# airball_sensor_board_v5.net
KiCad netlist of a schematic drawn in EAGLE
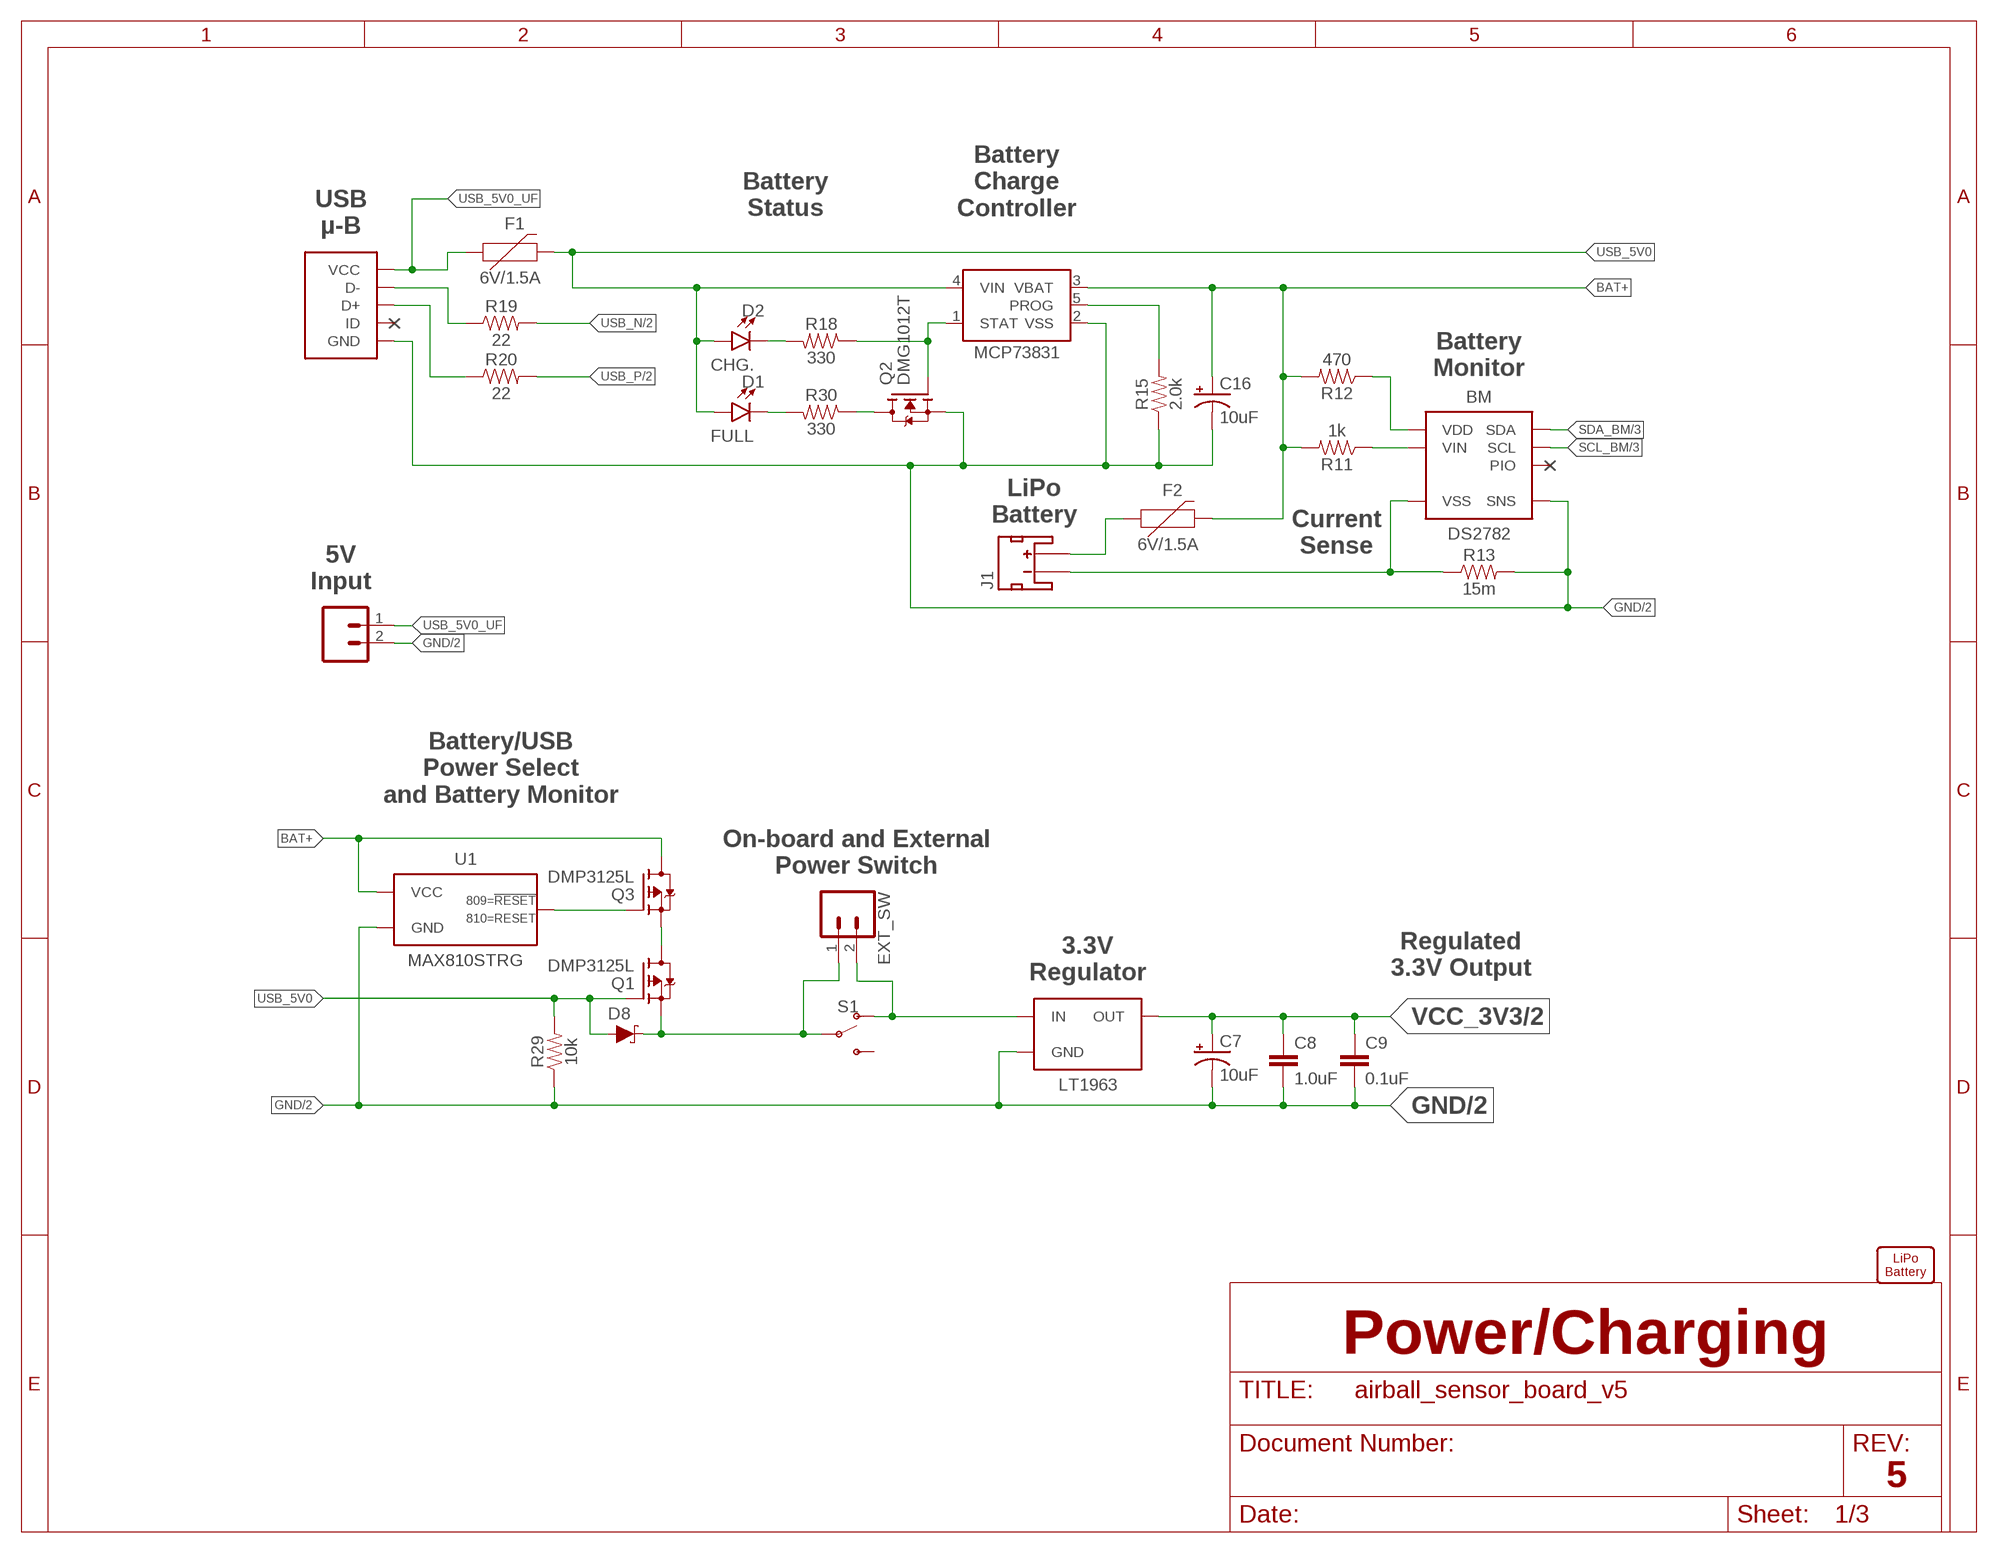
[diagram p0: schematic, sheet 1]
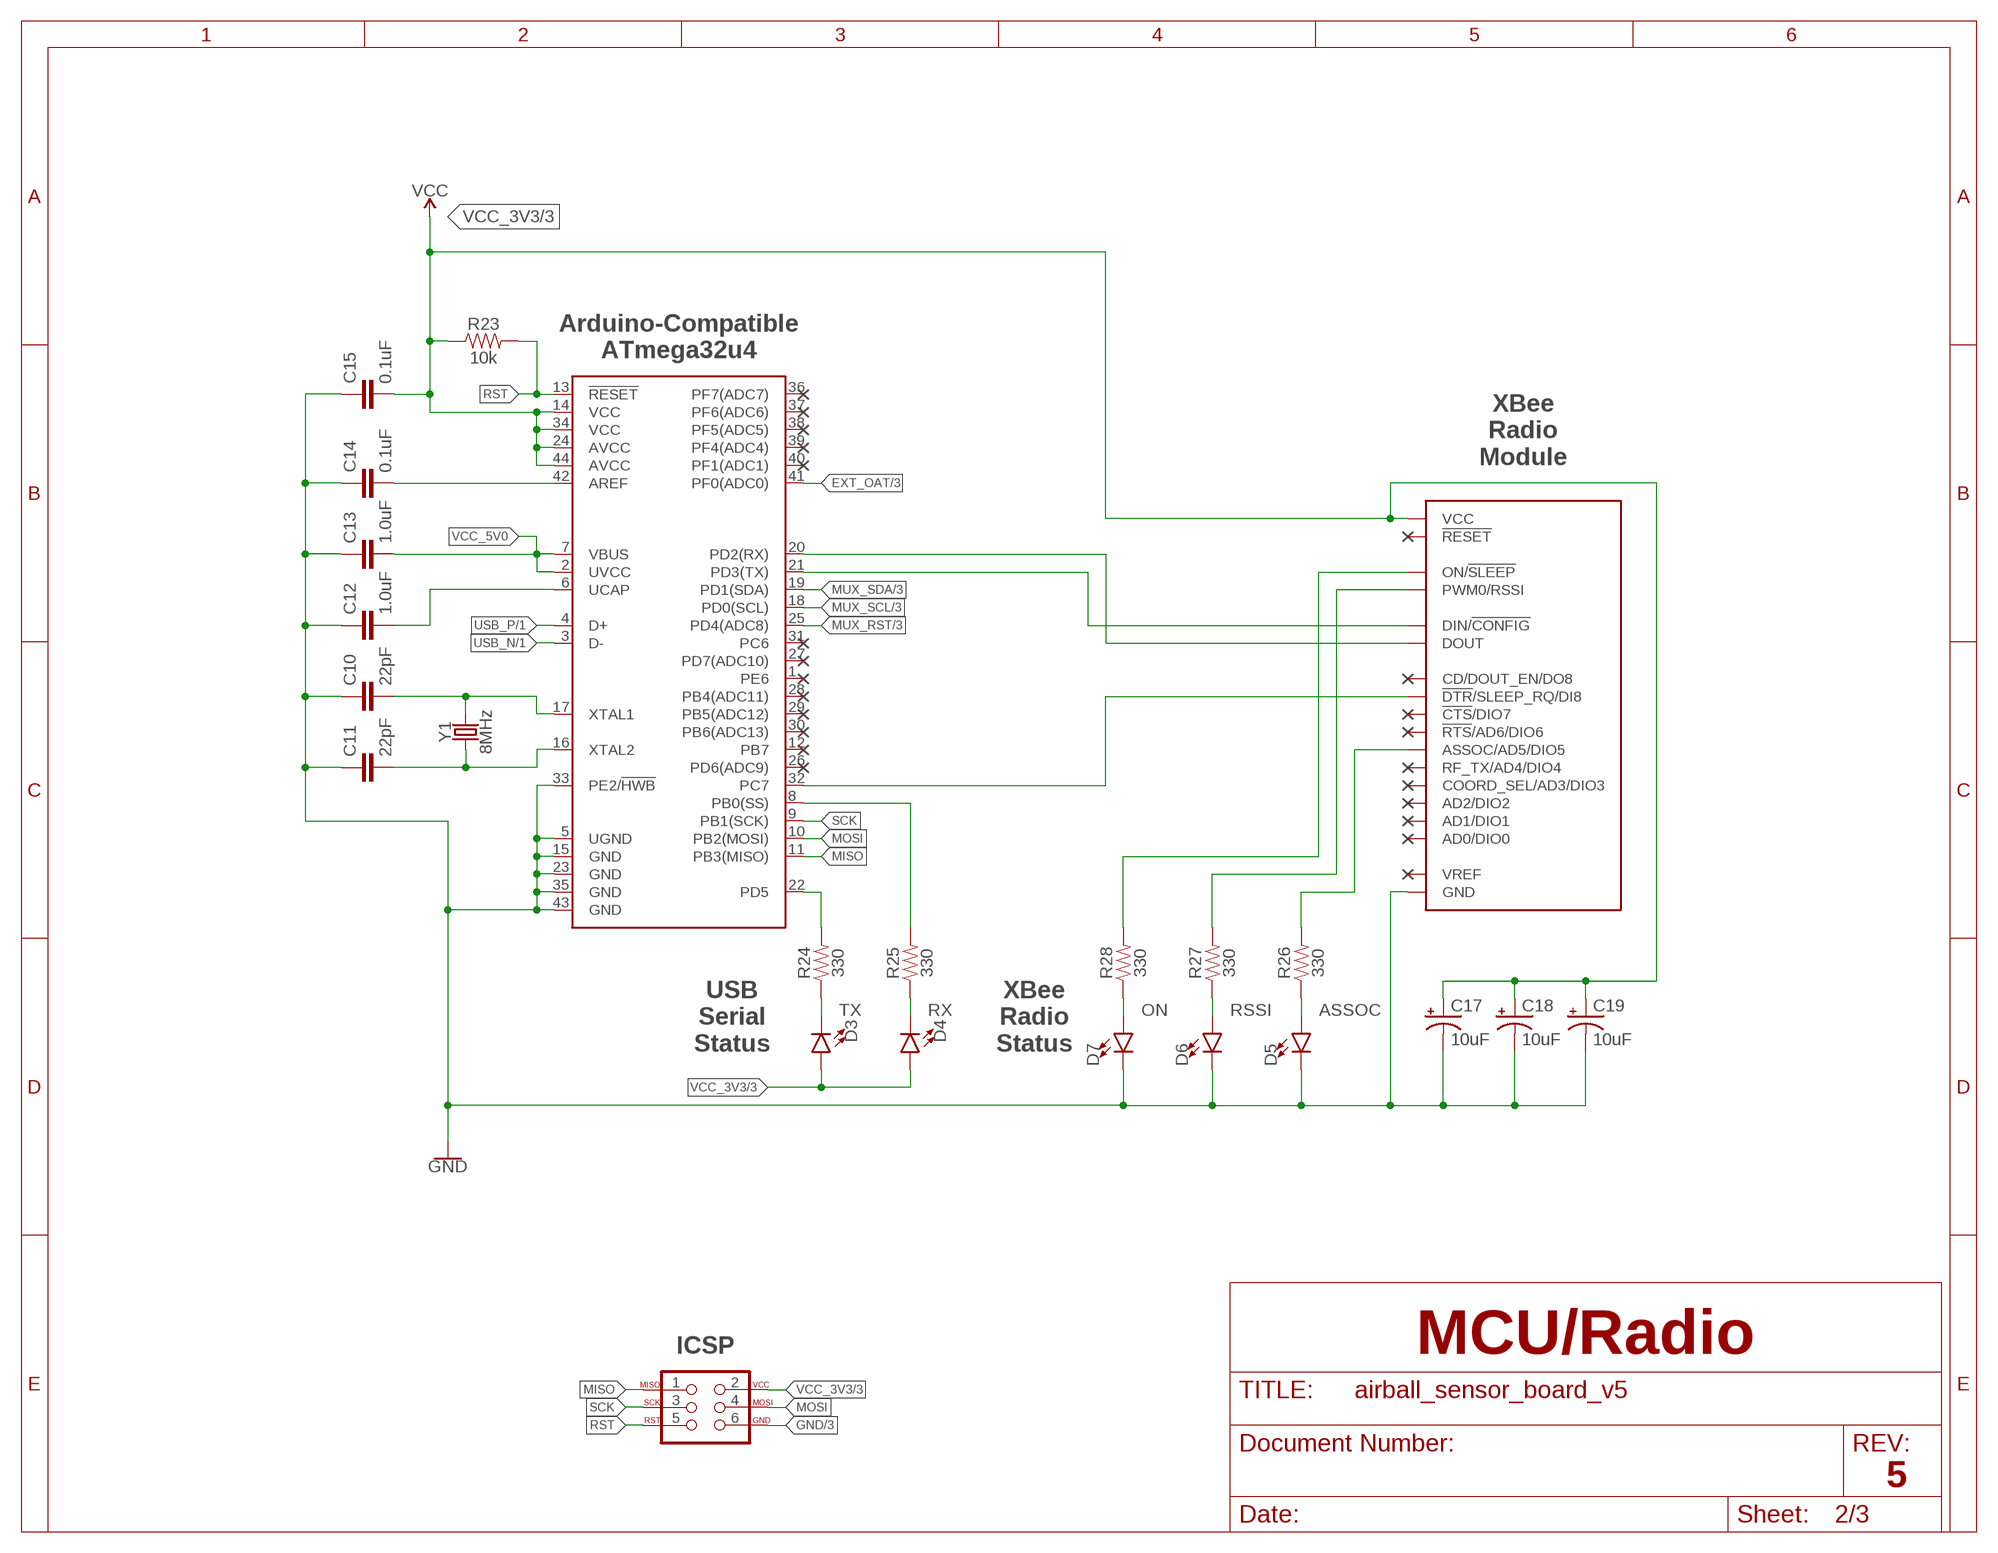
[diagram p1: schematic, sheet 2]
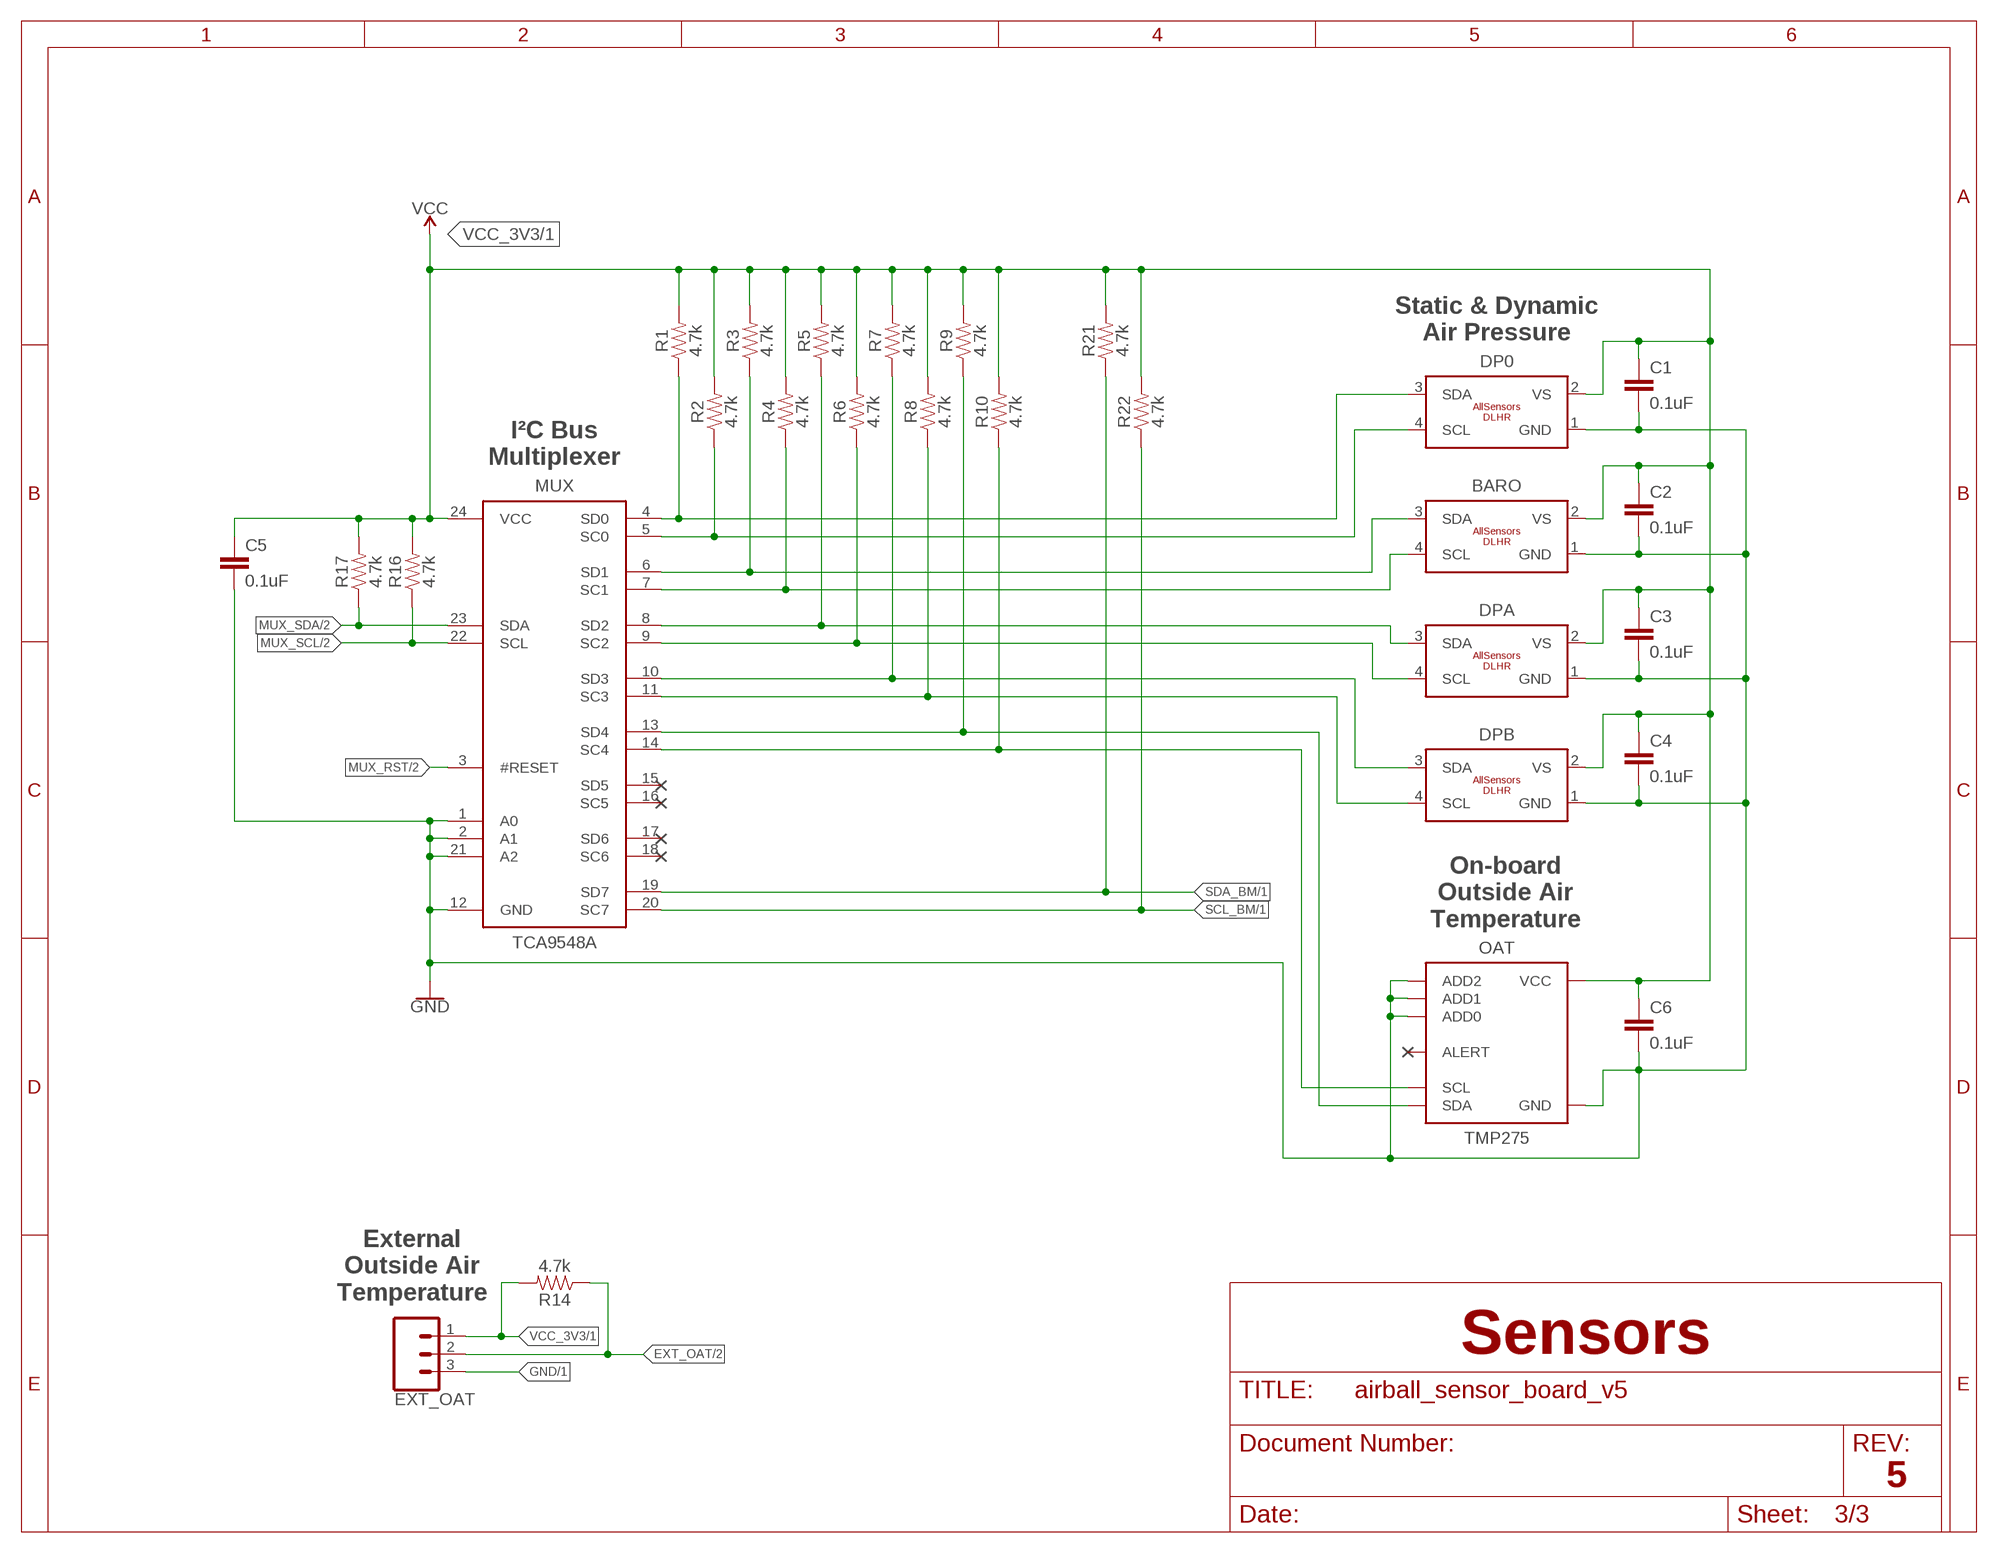
[diagram p2: schematic, sheet 3]

(export (version "E")
  (design (tool "Eeschema 10.0.6"))
  (components
    (comp (ref "BARO")
      (value "ALLSENSORS_DLHR_I2C-E1BD")
      (footprint "eagle-import:ALLSENSORS_E1BD")
      (libsource (lib "eagle-import") (part "ALLSENSORS_DLHR_I2C-E1BD"))
    )
    (comp (ref "C1")
      (value "0.1uF")
      (footprint "eagle-import:0603")
      (libsource (lib "eagle-import") (part "0.1UF-0603-25V-5%"))
    )
    (comp (ref "C2")
      (value "0.1uF")
      (footprint "eagle-import:0603")
      (libsource (lib "eagle-import") (part "0.1UF-0603-25V-5%"))
    )
    (comp (ref "C3")
      (value "0.1uF")
      (footprint "eagle-import:0603")
      (libsource (lib "eagle-import") (part "0.1UF-0603-25V-5%"))
    )
    (comp (ref "C4")
      (value "0.1uF")
      (footprint "eagle-import:0603")
      (libsource (lib "eagle-import") (part "0.1UF-0603-25V-5%"))
    )
    (comp (ref "C5")
      (value "0.1uF")
      (footprint "eagle-import:0603")
      (libsource (lib "eagle-import") (part "0.1UF-0603-25V-5%"))
    )
    (comp (ref "C6")
      (value "0.1uF")
      (footprint "eagle-import:0603")
      (libsource (lib "eagle-import") (part "0.1UF-0603-25V-5%"))
    )
    (comp (ref "DP0")
      (value "ALLSENSORS_DLHR_I2C-E1BD")
      (footprint "eagle-import:ALLSENSORS_E1BD")
      (libsource (lib "eagle-import") (part "ALLSENSORS_DLHR_I2C-E1BD"))
    )
    (comp (ref "DPA")
      (value "ALLSENSORS_DLHR_I2C-E1BD")
      (footprint "eagle-import:ALLSENSORS_E1BD")
      (libsource (lib "eagle-import") (part "ALLSENSORS_DLHR_I2C-E1BD"))
    )
    (comp (ref "DPB")
      (value "ALLSENSORS_DLHR_I2C-E1BD")
      (footprint "eagle-import:ALLSENSORS_E1BD")
      (libsource (lib "eagle-import") (part "ALLSENSORS_DLHR_I2C-E1BD"))
    )
    (comp (ref "EXT_OAT")
      (value "CONN_03")
      (footprint "eagle-import:1X03")
      (libsource (lib "eagle-import") (part "CONN_03"))
    )
    (comp (ref "MUX")
      (value "TCA9548A")
      (footprint "eagle-import:TSSOP24")
      (libsource (lib "eagle-import") (part "TCA9548ATSSOP24"))
    )
    (comp (ref "OAT")
      (value "TMP275")
      (footprint "eagle-import:SOIC8")
      (libsource (lib "eagle-import") (part "LM75-8PIN"))
    )
    (comp (ref "R1")
      (value "4.7k")
      (footprint "eagle-import:0603")
      (libsource (lib "eagle-import") (part "4.7KOHM-0603-1/10W-1%"))
    )
    (comp (ref "R2")
      (value "4.7k")
      (footprint "eagle-import:0603")
      (libsource (lib "eagle-import") (part "4.7KOHM-0603-1/10W-1%"))
    )
    (comp (ref "R3")
      (value "4.7k")
      (footprint "eagle-import:0603")
      (libsource (lib "eagle-import") (part "4.7KOHM-0603-1/10W-1%"))
    )
    (comp (ref "R4")
      (value "4.7k")
      (footprint "eagle-import:0603")
      (libsource (lib "eagle-import") (part "4.7KOHM-0603-1/10W-1%"))
    )
    (comp (ref "R5")
      (value "4.7k")
      (footprint "eagle-import:0603")
      (libsource (lib "eagle-import") (part "4.7KOHM-0603-1/10W-1%"))
    )
    (comp (ref "R6")
      (value "4.7k")
      (footprint "eagle-import:0603")
      (libsource (lib "eagle-import") (part "4.7KOHM-0603-1/10W-1%"))
    )
    (comp (ref "R7")
      (value "4.7k")
      (footprint "eagle-import:0603")
      (libsource (lib "eagle-import") (part "4.7KOHM-0603-1/10W-1%"))
    )
    (comp (ref "R8")
      (value "4.7k")
      (footprint "eagle-import:0603")
      (libsource (lib "eagle-import") (part "4.7KOHM-0603-1/10W-1%"))
    )
    (comp (ref "R9")
      (value "4.7k")
      (footprint "eagle-import:0603")
      (libsource (lib "eagle-import") (part "4.7KOHM-0603-1/10W-1%"))
    )
    (comp (ref "R10")
      (value "4.7k")
      (footprint "eagle-import:0603")
      (libsource (lib "eagle-import") (part "4.7KOHM-0603-1/10W-1%"))
    )
    (comp (ref "R14")
      (value "4.7k")
      (footprint "eagle-import:0603")
      (libsource (lib "eagle-import") (part "4.7KOHM-0603-1/10W-1%"))
    )
    (comp (ref "R16")
      (value "4.7k")
      (footprint "eagle-import:0603")
      (libsource (lib "eagle-import") (part "4.7KOHM-0603-1/10W-1%"))
    )
    (comp (ref "R17")
      (value "4.7k")
      (footprint "eagle-import:0603")
      (libsource (lib "eagle-import") (part "4.7KOHM-0603-1/10W-1%"))
    )
    (comp (ref "R21")
      (value "4.7k")
      (footprint "eagle-import:0603")
      (libsource (lib "eagle-import") (part "4.7KOHM-0603-1/10W-1%"))
    )
    (comp (ref "R22")
      (value "4.7k")
      (footprint "eagle-import:0603")
      (libsource (lib "eagle-import") (part "4.7KOHM-0603-1/10W-1%"))
    )
    (comp (ref "C10")
      (value "22pF")
      (footprint "eagle-import:0603")
      (libsource (lib "eagle-import") (part "22PF-0603-50V-5%"))
    )
    (comp (ref "C11")
      (value "22pF")
      (footprint "eagle-import:0603")
      (libsource (lib "eagle-import") (part "22PF-0603-50V-5%"))
    )
    (comp (ref "C12")
      (value "1.0uF")
      (footprint "eagle-import:0603")
      (libsource (lib "eagle-import") (part "1.0UF-0603-16V-10%"))
    )
    (comp (ref "C13")
      (value "1.0uF")
      (footprint "eagle-import:0603")
      (libsource (lib "eagle-import") (part "1.0UF-0603-16V-10%"))
    )
    (comp (ref "C14")
      (value "0.1uF")
      (footprint "eagle-import:0603")
      (libsource (lib "eagle-import") (part "0.1UF-0603-25V-5%"))
    )
    (comp (ref "C15")
      (value "0.1uF")
      (footprint "eagle-import:0603")
      (libsource (lib "eagle-import") (part "0.1UF-0603-25V-5%"))
    )
    (comp (ref "C17")
      (value "10uF")
      (footprint "eagle-import:EIA3216")
      (libsource (lib "eagle-import") (part "10UF-POLAR-EIA3216-16V-10%(TANT)"))
    )
    (comp (ref "C18")
      (value "10uF")
      (footprint "eagle-import:EIA3216")
      (libsource (lib "eagle-import") (part "10UF-POLAR-EIA3216-16V-10%(TANT)"))
    )
    (comp (ref "C19")
      (value "10uF")
      (footprint "eagle-import:EIA3216")
      (libsource (lib "eagle-import") (part "10UF-POLAR-EIA3216-16V-10%(TANT)"))
    )
    (comp (ref "D3")
      (value "LED0603")
      (footprint "eagle-import:LED-0603")
      (libsource (lib "eagle-import") (part "LED0603"))
    )
    (comp (ref "D4")
      (value "LED0603")
      (footprint "eagle-import:LED-0603")
      (libsource (lib "eagle-import") (part "LED0603"))
    )
    (comp (ref "D5")
      (value "LED0603")
      (footprint "eagle-import:LED-0603")
      (libsource (lib "eagle-import") (part "LED0603"))
    )
    (comp (ref "D6")
      (value "LED0603")
      (footprint "eagle-import:LED-0603")
      (libsource (lib "eagle-import") (part "LED0603"))
    )
    (comp (ref "D7")
      (value "LED0603")
      (footprint "eagle-import:LED-0603")
      (libsource (lib "eagle-import") (part "LED0603"))
    )
    (comp (ref "ICSP")
      (value "AVR_SPI_PROG_3X2PTH")
      (footprint "eagle-import:2X3")
      (libsource (lib "eagle-import") (part "AVR_SPI_PROG_3X2PTH"))
    )
    (comp (ref "MCU")
      (value "32U4")
      (footprint "eagle-import:TQFP44")
      (libsource (lib "eagle-import") (part "ATMEGA32U4TQFP-44"))
    )
    (comp (ref "R23")
      (value "10k")
      (footprint "eagle-import:0603")
      (libsource (lib "eagle-import") (part "10KOHM-0603-1/10W-1%"))
    )
    (comp (ref "R24")
      (value "330")
      (footprint "eagle-import:0603")
      (libsource (lib "eagle-import") (part "330OHM-0603-1/10W-1%"))
    )
    (comp (ref "R25")
      (value "330")
      (footprint "eagle-import:0603")
      (libsource (lib "eagle-import") (part "330OHM-0603-1/10W-1%"))
    )
    (comp (ref "R26")
      (value "330")
      (footprint "eagle-import:0603")
      (libsource (lib "eagle-import") (part "330OHM-0603-1/10W-1%"))
    )
    (comp (ref "R27")
      (value "330")
      (footprint "eagle-import:0603")
      (libsource (lib "eagle-import") (part "330OHM-0603-1/10W-1%"))
    )
    (comp (ref "R28")
      (value "330")
      (footprint "eagle-import:0603")
      (libsource (lib "eagle-import") (part "330OHM-0603-1/10W-1%"))
    )
    (comp (ref "XBEE")
      (value "XBEE-PRO-SMD")
      (footprint "eagle-import:XBEE-PRO-SMD")
      (libsource (lib "eagle-import") (part "XBEE-PRO-SMD"))
    )
    (comp (ref "Y1")
      (value "8MHz")
      (footprint "eagle-import:CRYSTAL-SMD-5X3.2-4PAD")
      (libsource (lib "eagle-import") (part "CRYSTAL-8MHZSMD-5X3.2"))
    )
    (comp (ref "BM")
      (value "DS2782")
      (footprint "eagle-import:TSSOP8")
      (libsource (lib "eagle-import") (part "DS2782"))
    )
    (comp (ref "C7")
      (value "10uF")
      (footprint "eagle-import:EIA3216")
      (libsource (lib "eagle-import") (part "10UF-POLAR-EIA3216-16V-10%(TANT)"))
    )
    (comp (ref "C8")
      (value "1.0uF")
      (footprint "eagle-import:0603")
      (libsource (lib "eagle-import") (part "1.0UF-0603-16V-10%"))
    )
    (comp (ref "C9")
      (value "0.1uF")
      (footprint "eagle-import:0603")
      (libsource (lib "eagle-import") (part "0.1UF-0603-25V-5%"))
    )
    (comp (ref "C16")
      (value "10uF")
      (footprint "eagle-import:EIA3216")
      (libsource (lib "eagle-import") (part "10UF-POLAR-EIA3216-16V-10%(TANT)"))
    )
    (comp (ref "CC")
      (value "MCP73831")
      (footprint "eagle-import:SOT23-5")
      (libsource (lib "eagle-import") (part "MCP73831"))
    )
    (comp (ref "D1")
      (value "LED0603")
      (footprint "eagle-import:LED-0603")
      (libsource (lib "eagle-import") (part "LED0603"))
    )
    (comp (ref "D2")
      (value "LED0603")
      (footprint "eagle-import:LED-0603")
      (libsource (lib "eagle-import") (part "LED0603"))
    )
    (comp (ref "D8")
      (value "DIODE-SCHOTTKY-BAT20J")
      (footprint "eagle-import:SOD-323")
      (libsource (lib "eagle-import") (part "DIODE-SCHOTTKY-BAT20J"))
    )
    (comp (ref "EXT_POWER")
      (value "CONN_02")
      (footprint "eagle-import:1X02")
      (libsource (lib "eagle-import") (part "CONN_02"))
    )
    (comp (ref "EXT_SW")
      (value "CONN_02")
      (footprint "eagle-import:1X02")
      (libsource (lib "eagle-import") (part "CONN_02"))
    )
    (comp (ref "F1")
      (value "6V/1.5A")
      (footprint "eagle-import:1206")
      (libsource (lib "eagle-import") (part "PPTC_HALF-AMP"))
    )
    (comp (ref "F2")
      (value "6V/1.5A")
      (footprint "eagle-import:1206")
      (libsource (lib "eagle-import") (part "PPTC_HALF-AMP"))
    )
    (comp (ref "J1")
      (value "JST_2MM_MALE")
      (footprint "eagle-import:JST-2-SMD")
      (libsource (lib "eagle-import") (part "JST_2MM_MALE"))
    )
    (comp (ref "JP1")
      (value "USB_MICROB_PLUG")
      (footprint "eagle-import:USB_MICRO_B_TYCO")
      (libsource (lib "eagle-import") (part "USB_MICROB_PLUG"))
    )
    (comp (ref "Q1")
      (value "DMP3125L")
      (footprint "eagle-import:SOT23-3")
      (libsource (lib "eagle-import") (part "DMP3125L"))
    )
    (comp (ref "Q2")
      (value "DMG1012T")
      (footprint "eagle-import:SOT523-3")
      (libsource (lib "eagle-import") (part "DMG1012T"))
    )
    (comp (ref "Q3")
      (value "DMP3125L")
      (footprint "eagle-import:SOT23-3")
      (libsource (lib "eagle-import") (part "DMP3125L"))
    )
    (comp (ref "R11")
      (value "1k")
      (footprint "eagle-import:0603")
      (libsource (lib "eagle-import") (part "1KOHM-0603-1/10W-1%"))
    )
    (comp (ref "R12")
      (value "470")
      (footprint "eagle-import:0603")
      (libsource (lib "eagle-import") (part "470OHM-0603-1/10W-1%"))
    )
    (comp (ref "R13")
      (value "15m")
      (footprint "eagle-import:1206")
      (libsource (lib "eagle-import") (part "RESISTOR1206"))
    )
    (comp (ref "R15")
      (value "2.0k")
      (footprint "eagle-import:0603")
      (libsource (lib "eagle-import") (part "2.0KOHM-0603-1/10W-5%"))
    )
    (comp (ref "R18")
      (value "330")
      (footprint "eagle-import:0603")
      (libsource (lib "eagle-import") (part "330OHM-0603-1/10W-1%"))
    )
    (comp (ref "R19")
      (value "22")
      (footprint "eagle-import:0603")
      (libsource (lib "eagle-import") (part "22OHM-0603-1/10W-1%"))
    )
    (comp (ref "R20")
      (value "22")
      (footprint "eagle-import:0603")
      (libsource (lib "eagle-import") (part "22OHM-0603-1/10W-1%"))
    )
    (comp (ref "R29")
      (value "10k")
      (footprint "eagle-import:0603")
      (libsource (lib "eagle-import") (part "10KOHM-0603-1/10W-1%"))
    )
    (comp (ref "R30")
      (value "330")
      (footprint "eagle-import:0603")
      (libsource (lib "eagle-import") (part "330OHM-0603-1/10W-1%"))
    )
    (comp (ref "S1")
      (value "SWITCH-SPDT-SMD-RIGHT-ANGLE")
      (footprint "eagle-import:SWITCH_SPST_SMD_A")
      (libsource (lib "eagle-import") (part "SWITCH-SPDT-SMD-RIGHT-ANGLE"))
    )
    (comp (ref "U$3")
      (value "LIPO_BATTERY_OUTLINE-1000MAH")
      (footprint "eagle-import:SPARKFUN_LIPO_1000MAH")
      (libsource (lib "eagle-import") (part "LIPO_BATTERY_OUTLINE-1000MAH"))
    )
    (comp (ref "U1")
      (value "MAX810STRG")
      (footprint "eagle-import:SOT23-3")
      (libsource (lib "eagle-import") (part "MAX809/810"))
    )
    (comp (ref "VREG")
      (value "LT1963")
      (footprint "eagle-import:SOT223-3")
      (libsource (lib "eagle-import") (part "LT1963"))
    )
  )
  (nets
    (net (code "1") (name "BAT+") (class "Default")
      (node (ref "C16") (pin "+") (pinfunction "+_+") (pintype "passive"))
      (node (ref "CC") (pin "3") (pinfunction "VBAT_3") (pintype "power_in"))
      (node (ref "F2") (pin "2") (pinfunction "2_2") (pintype "bidirectional"))
      (node (ref "Q3") (pin "3") (pinfunction "D_3") (pintype "passive"))
      (node (ref "R11") (pin "2") (pinfunction "2_2") (pintype "passive"))
      (node (ref "R12") (pin "2") (pinfunction "2_2") (pintype "passive"))
      (node (ref "U1") (pin "3") (pinfunction "VCC_3") (pintype "bidirectional"))
    )
    (net (code "2") (name "EXT_OAT") (class "Default")
      (node (ref "EXT_OAT") (pin "2") (pinfunction "2_2") (pintype "passive"))
      (node (ref "MCU") (pin "41") (pinfunction "PF0(ADC0)_41") (pintype "bidirectional"))
      (node (ref "R14") (pin "1") (pinfunction "1_1") (pintype "passive"))
    )
    (net (code "3") (name "GND") (class "Default")
      (node (ref "BARO") (pin "1") (pinfunction "GND_1") (pintype "power_in"))
      (node (ref "BM") (pin "7") (pinfunction "SNS_7") (pintype "power_in"))
      (node (ref "C1") (pin "2") (pinfunction "2_2") (pintype "passive"))
      (node (ref "C10") (pin "1") (pinfunction "1_1") (pintype "passive"))
      (node (ref "C11") (pin "1") (pinfunction "1_1") (pintype "passive"))
      (node (ref "C12") (pin "1") (pinfunction "1_1") (pintype "passive"))
      (node (ref "C13") (pin "1") (pinfunction "1_1") (pintype "passive"))
      (node (ref "C14") (pin "1") (pinfunction "1_1") (pintype "passive"))
      (node (ref "C15") (pin "1") (pinfunction "1_1") (pintype "passive"))
      (node (ref "C16") (pin "-") (pinfunction "-_-") (pintype "passive"))
      (node (ref "C17") (pin "-") (pinfunction "-_-") (pintype "passive"))
      (node (ref "C18") (pin "-") (pinfunction "-_-") (pintype "passive"))
      (node (ref "C19") (pin "-") (pinfunction "-_-") (pintype "passive"))
      (node (ref "C2") (pin "2") (pinfunction "2_2") (pintype "passive"))
      (node (ref "C3") (pin "2") (pinfunction "2_2") (pintype "passive"))
      (node (ref "C4") (pin "2") (pinfunction "2_2") (pintype "passive"))
      (node (ref "C5") (pin "2") (pinfunction "2_2") (pintype "passive"))
      (node (ref "C6") (pin "2") (pinfunction "2_2") (pintype "passive"))
      (node (ref "C7") (pin "-") (pinfunction "-_-") (pintype "passive"))
      (node (ref "C8") (pin "2") (pinfunction "2_2") (pintype "passive"))
      (node (ref "C9") (pin "2") (pinfunction "2_2") (pintype "passive"))
      (node (ref "CC") (pin "2") (pinfunction "VSS_2") (pintype "power_in"))
      (node (ref "D5") (pin "C") (pinfunction "C_C") (pintype "passive"))
      (node (ref "D6") (pin "C") (pinfunction "C_C") (pintype "passive"))
      (node (ref "D7") (pin "C") (pinfunction "C_C") (pintype "passive"))
      (node (ref "DP0") (pin "1") (pinfunction "GND_1") (pintype "power_in"))
      (node (ref "DPA") (pin "1") (pinfunction "GND_1") (pintype "power_in"))
      (node (ref "DPB") (pin "1") (pinfunction "GND_1") (pintype "power_in"))
      (node (ref "EXT_OAT") (pin "3") (pinfunction "3_3") (pintype "passive"))
      (node (ref "EXT_POWER") (pin "2") (pinfunction "2_2") (pintype "passive"))
      (node (ref "ICSP") (pin "6") (pinfunction "6_6") (pintype "passive"))
      (node (ref "JP1") (pin "5") (pinfunction "GND_5") (pintype "power_in"))
      (node (ref "JP1") (pin "SH@1") (pinfunction "GND_SH@1") (pintype "power_in"))
      (node (ref "JP1") (pin "SH@2") (pinfunction "GND_SH@2") (pintype "power_in"))
      (node (ref "JP1") (pin "SH@3") (pinfunction "GND_SH@3") (pintype "power_in"))
      (node (ref "JP1") (pin "SH@4") (pinfunction "GND_SH@4") (pintype "power_in"))
      (node (ref "MCU") (pin "15") (pinfunction "GND_15") (pintype "bidirectional"))
      (node (ref "MCU") (pin "23") (pinfunction "GND_23") (pintype "bidirectional"))
      (node (ref "MCU") (pin "33") (pinfunction "PE2/~{HWB}_33") (pintype "bidirectional"))
      (node (ref "MCU") (pin "35") (pinfunction "GND_35") (pintype "bidirectional"))
      (node (ref "MCU") (pin "43") (pinfunction "GND_43") (pintype "bidirectional"))
      (node (ref "MCU") (pin "5") (pinfunction "UGND_5") (pintype "bidirectional"))
      (node (ref "MUX") (pin "1") (pinfunction "A0_1") (pintype "bidirectional"))
      (node (ref "MUX") (pin "12") (pinfunction "GND_12") (pintype "bidirectional"))
      (node (ref "MUX") (pin "2") (pinfunction "A1_2") (pintype "bidirectional"))
      (node (ref "MUX") (pin "21") (pinfunction "A2_21") (pintype "bidirectional"))
      (node (ref "OAT") (pin "4") (pinfunction "GND_4") (pintype "power_in"))
      (node (ref "OAT") (pin "5") (pinfunction "ADD2_5") (pintype "input"))
      (node (ref "OAT") (pin "6") (pinfunction "ADD1_6") (pintype "input"))
      (node (ref "OAT") (pin "7") (pinfunction "ADD0_7") (pintype "input"))
      (node (ref "Q2") (pin "3") (pinfunction "S_3") (pintype "passive"))
      (node (ref "R13") (pin "2") (pinfunction "2_2") (pintype "passive"))
      (node (ref "R15") (pin "1") (pinfunction "1_1") (pintype "passive"))
      (node (ref "R29") (pin "1") (pinfunction "1_1") (pintype "passive"))
      (node (ref "U1") (pin "1") (pinfunction "GND_1") (pintype "bidirectional"))
      (node (ref "VREG") (pin "2") (pinfunction "GND_2") (pintype "power_in"))
      (node (ref "VREG") (pin "TAB") (pinfunction "GND_TAB") (pintype "power_in"))
      (node (ref "XBEE") (pin "10") (pinfunction "GND_10") (pintype "power_in"))
    )
    (net (code "4") (name "MISO") (class "Default")
      (node (ref "ICSP") (pin "1") (pinfunction "1_1") (pintype "passive"))
      (node (ref "MCU") (pin "11") (pinfunction "PB3(MISO)_11") (pintype "bidirectional"))
    )
    (net (code "5") (name "MOSI") (class "Default")
      (node (ref "ICSP") (pin "4") (pinfunction "4_4") (pintype "passive"))
      (node (ref "MCU") (pin "10") (pinfunction "PB2(MOSI)_10") (pintype "bidirectional"))
    )
    (net (code "6") (name "MUX_RST") (class "Default")
      (node (ref "MCU") (pin "25") (pinfunction "PD4(ADC8)_25") (pintype "bidirectional"))
      (node (ref "MUX") (pin "3") (pinfunction "#RESET_3") (pintype "bidirectional"))
    )
    (net (code "7") (name "MUX_SCL") (class "Default")
      (node (ref "MCU") (pin "18") (pinfunction "PD0(SCL)_18") (pintype "bidirectional"))
      (node (ref "MUX") (pin "22") (pinfunction "SCL_22") (pintype "bidirectional"))
      (node (ref "R16") (pin "1") (pinfunction "1_1") (pintype "passive"))
    )
    (net (code "8") (name "MUX_SDA") (class "Default")
      (node (ref "MCU") (pin "19") (pinfunction "PD1(SDA)_19") (pintype "bidirectional"))
      (node (ref "MUX") (pin "23") (pinfunction "SDA_23") (pintype "bidirectional"))
      (node (ref "R17") (pin "1") (pinfunction "1_1") (pintype "passive"))
    )
    (net (code "9") (name "Net-(BARO-SCL)") (class "Default")
      (node (ref "BARO") (pin "4") (pinfunction "SCL_4") (pintype "bidirectional"))
      (node (ref "MUX") (pin "7") (pinfunction "SC1_7") (pintype "bidirectional"))
      (node (ref "R4") (pin "1") (pinfunction "1_1") (pintype "passive"))
    )
    (net (code "10") (name "Net-(BARO-SDA)") (class "Default")
      (node (ref "BARO") (pin "3") (pinfunction "SDA_3") (pintype "bidirectional"))
      (node (ref "MUX") (pin "6") (pinfunction "SD1_6") (pintype "bidirectional"))
      (node (ref "R3") (pin "1") (pinfunction "1_1") (pintype "passive"))
    )
    (net (code "11") (name "Net-(BM-VDD)") (class "Default")
      (node (ref "BM") (pin "4") (pinfunction "VDD_4") (pintype "power_in"))
      (node (ref "R12") (pin "1") (pinfunction "1_1") (pintype "passive"))
    )
    (net (code "12") (name "Net-(BM-VIN)") (class "Default")
      (node (ref "BM") (pin "3") (pinfunction "VIN_3") (pintype "power_in"))
      (node (ref "R11") (pin "1") (pinfunction "1_1") (pintype "passive"))
    )
    (net (code "13") (name "Net-(BM-VSS)") (class "Default")
      (node (ref "BM") (pin "2") (pinfunction "VSS_2") (pintype "power_in"))
      (node (ref "J1") (pin "1") (pinfunction "-_1") (pintype "bidirectional"))
      (node (ref "R13") (pin "1") (pinfunction "1_1") (pintype "passive"))
    )
    (net (code "14") (name "Net-(CC-PROG)") (class "Default")
      (node (ref "CC") (pin "5") (pinfunction "PROG_5") (pintype "input"))
      (node (ref "R15") (pin "2") (pinfunction "2_2") (pintype "passive"))
    )
    (net (code "15") (name "Net-(CC-STAT)") (class "Default")
      (node (ref "CC") (pin "1") (pinfunction "STAT_1") (pintype "output"))
      (node (ref "Q2") (pin "1") (pinfunction "G_1") (pintype "passive"))
      (node (ref "R18") (pin "1") (pinfunction "1_1") (pintype "passive"))
    )
    (net (code "16") (name "Net-(D1-PadC)") (class "Default")
      (node (ref "D1") (pin "C") (pinfunction "C_C") (pintype "passive"))
      (node (ref "R30") (pin "2") (pinfunction "2_2") (pintype "passive"))
    )
    (net (code "17") (name "Net-(D2-PadC)") (class "Default")
      (node (ref "D2") (pin "C") (pinfunction "C_C") (pintype "passive"))
      (node (ref "R18") (pin "2") (pinfunction "2_2") (pintype "passive"))
    )
    (net (code "18") (name "Net-(D3-PadC)") (class "Default")
      (node (ref "D3") (pin "C") (pinfunction "C_C") (pintype "passive"))
      (node (ref "R24") (pin "1") (pinfunction "1_1") (pintype "passive"))
    )
    (net (code "19") (name "Net-(D4-PadC)") (class "Default")
      (node (ref "D4") (pin "C") (pinfunction "C_C") (pintype "passive"))
      (node (ref "R25") (pin "1") (pinfunction "1_1") (pintype "passive"))
    )
    (net (code "20") (name "Net-(D5-PadA)") (class "Default")
      (node (ref "D5") (pin "A") (pinfunction "A_A") (pintype "passive"))
      (node (ref "R26") (pin "1") (pinfunction "1_1") (pintype "passive"))
    )
    (net (code "21") (name "Net-(D6-PadA)") (class "Default")
      (node (ref "D6") (pin "A") (pinfunction "A_A") (pintype "passive"))
      (node (ref "R27") (pin "1") (pinfunction "1_1") (pintype "passive"))
    )
    (net (code "22") (name "Net-(D7-PadA)") (class "Default")
      (node (ref "D7") (pin "A") (pinfunction "A_A") (pintype "passive"))
      (node (ref "R28") (pin "1") (pinfunction "1_1") (pintype "passive"))
    )
    (net (code "23") (name "Net-(DP0-SCL)") (class "Default")
      (node (ref "DP0") (pin "4") (pinfunction "SCL_4") (pintype "bidirectional"))
      (node (ref "MUX") (pin "5") (pinfunction "SC0_5") (pintype "bidirectional"))
      (node (ref "R2") (pin "1") (pinfunction "1_1") (pintype "passive"))
    )
    (net (code "24") (name "Net-(DP0-SDA)") (class "Default")
      (node (ref "DP0") (pin "3") (pinfunction "SDA_3") (pintype "bidirectional"))
      (node (ref "MUX") (pin "4") (pinfunction "SD0_4") (pintype "bidirectional"))
      (node (ref "R1") (pin "1") (pinfunction "1_1") (pintype "passive"))
    )
    (net (code "25") (name "Net-(DPA-SCL)") (class "Default")
      (node (ref "DPA") (pin "4") (pinfunction "SCL_4") (pintype "bidirectional"))
      (node (ref "MUX") (pin "9") (pinfunction "SC2_9") (pintype "bidirectional"))
      (node (ref "R6") (pin "1") (pinfunction "1_1") (pintype "passive"))
    )
    (net (code "26") (name "Net-(DPA-SDA)") (class "Default")
      (node (ref "DPA") (pin "3") (pinfunction "SDA_3") (pintype "bidirectional"))
      (node (ref "MUX") (pin "8") (pinfunction "SD2_8") (pintype "bidirectional"))
      (node (ref "R5") (pin "1") (pinfunction "1_1") (pintype "passive"))
    )
    (net (code "27") (name "Net-(DPB-SCL)") (class "Default")
      (node (ref "DPB") (pin "4") (pinfunction "SCL_4") (pintype "bidirectional"))
      (node (ref "MUX") (pin "11") (pinfunction "SC3_11") (pintype "bidirectional"))
      (node (ref "R8") (pin "1") (pinfunction "1_1") (pintype "passive"))
    )
    (net (code "28") (name "Net-(DPB-SDA)") (class "Default")
      (node (ref "DPB") (pin "3") (pinfunction "SDA_3") (pintype "bidirectional"))
      (node (ref "MUX") (pin "10") (pinfunction "SD3_10") (pintype "bidirectional"))
      (node (ref "R7") (pin "1") (pinfunction "1_1") (pintype "passive"))
    )
    (net (code "29") (name "Net-(J1-+)") (class "Default")
      (node (ref "F2") (pin "1") (pinfunction "1_1") (pintype "bidirectional"))
      (node (ref "J1") (pin "2") (pinfunction "+_2") (pintype "bidirectional"))
    )
    (net (code "30") (name "Net-(JP1-D+)") (class "Default")
      (node (ref "JP1") (pin "3") (pinfunction "D+_3") (pintype "bidirectional"))
      (node (ref "R20") (pin "1") (pinfunction "1_1") (pintype "passive"))
    )
    (net (code "31") (name "Net-(JP1-D-)") (class "Default")
      (node (ref "JP1") (pin "2") (pinfunction "D-_2") (pintype "bidirectional"))
      (node (ref "R19") (pin "1") (pinfunction "1_1") (pintype "passive"))
    )
    (net (code "32") (name "Net-(MCU-AREF)") (class "Default")
      (node (ref "C14") (pin "2") (pinfunction "2_2") (pintype "passive"))
      (node (ref "MCU") (pin "42") (pinfunction "AREF_42") (pintype "bidirectional"))
    )
    (net (code "33") (name "Net-(MCU-PB0(SS))") (class "Default")
      (node (ref "MCU") (pin "8") (pinfunction "PB0(SS)_8") (pintype "bidirectional"))
      (node (ref "R25") (pin "2") (pinfunction "2_2") (pintype "passive"))
    )
    (net (code "34") (name "Net-(MCU-PC7)") (class "Default")
      (node (ref "MCU") (pin "32") (pinfunction "PC7_32") (pintype "bidirectional"))
      (node (ref "XBEE") (pin "9") (pinfunction "~{DTR}/SLEEP_RQ/DI8_9") (pintype "bidirectional"))
    )
    (net (code "35") (name "Net-(MCU-PD2(RX))") (class "Default")
      (node (ref "MCU") (pin "20") (pinfunction "PD2(RX)_20") (pintype "bidirectional"))
      (node (ref "XBEE") (pin "2") (pinfunction "DOUT_2") (pintype "output"))
    )
    (net (code "36") (name "Net-(MCU-PD3(TX))") (class "Default")
      (node (ref "MCU") (pin "21") (pinfunction "PD3(TX)_21") (pintype "bidirectional"))
      (node (ref "XBEE") (pin "3") (pinfunction "DIN/~{CONFIG}_3") (pintype "input"))
    )
    (net (code "37") (name "Net-(MCU-PD5)") (class "Default")
      (node (ref "MCU") (pin "22") (pinfunction "PD5_22") (pintype "bidirectional"))
      (node (ref "R24") (pin "2") (pinfunction "2_2") (pintype "passive"))
    )
    (net (code "38") (name "Net-(MCU-UCAP)") (class "Default")
      (node (ref "C12") (pin "2") (pinfunction "2_2") (pintype "passive"))
      (node (ref "MCU") (pin "6") (pinfunction "UCAP_6") (pintype "bidirectional"))
    )
    (net (code "39") (name "Net-(MCU-XTAL1)") (class "Default")
      (node (ref "C10") (pin "2") (pinfunction "2_2") (pintype "passive"))
      (node (ref "MCU") (pin "17") (pinfunction "XTAL1_17") (pintype "bidirectional"))
      (node (ref "Y1") (pin "3") (pinfunction "2_3") (pintype "passive"))
    )
    (net (code "40") (name "Net-(MCU-XTAL2)") (class "Default")
      (node (ref "C11") (pin "2") (pinfunction "2_2") (pintype "passive"))
      (node (ref "MCU") (pin "16") (pinfunction "XTAL2_16") (pintype "bidirectional"))
      (node (ref "Y1") (pin "1") (pinfunction "1_1") (pintype "passive"))
    )
    (net (code "41") (name "Net-(MUX-SC4)") (class "Default")
      (node (ref "MUX") (pin "14") (pinfunction "SC4_14") (pintype "bidirectional"))
      (node (ref "OAT") (pin "2") (pinfunction "SCL_2") (pintype "input"))
      (node (ref "R10") (pin "1") (pinfunction "1_1") (pintype "passive"))
    )
    (net (code "42") (name "Net-(MUX-SD4)") (class "Default")
      (node (ref "MUX") (pin "13") (pinfunction "SD4_13") (pintype "bidirectional"))
      (node (ref "OAT") (pin "1") (pinfunction "SDA_1") (pintype "bidirectional"))
      (node (ref "R9") (pin "1") (pinfunction "1_1") (pintype "passive"))
    )
    (net (code "43") (name "Net-(Q1-D)") (class "Default")
      (node (ref "Q1") (pin "3") (pinfunction "D_3") (pintype "passive"))
      (node (ref "Q3") (pin "2") (pinfunction "S_2") (pintype "passive"))
    )
    (net (code "44") (name "Net-(Q1-S)") (class "Default")
      (node (ref "D8") (pin "C") (pinfunction "C_C") (pintype "passive"))
      (node (ref "EXT_SW") (pin "1") (pinfunction "1_1") (pintype "passive"))
      (node (ref "Q1") (pin "2") (pinfunction "S_2") (pintype "passive"))
      (node (ref "S1") (pin "2") (pinfunction "P_2") (pintype "passive"))
    )
    (net (code "45") (name "Net-(Q2-D)") (class "Default")
      (node (ref "Q2") (pin "2") (pinfunction "D_2") (pintype "passive"))
      (node (ref "R30") (pin "1") (pinfunction "1_1") (pintype "passive"))
    )
    (net (code "46") (name "Net-(Q3-G)") (class "Default")
      (node (ref "Q3") (pin "1") (pinfunction "G_1") (pintype "passive"))
      (node (ref "U1") (pin "2") (pinfunction "RESET_2") (pintype "bidirectional"))
    )
    (net (code "47") (name "Net-(S1-O)") (class "Default")
      (node (ref "EXT_SW") (pin "2") (pinfunction "2_2") (pintype "passive"))
      (node (ref "S1") (pin "1") (pinfunction "O_1") (pintype "passive"))
      (node (ref "VREG") (pin "1") (pinfunction "IN_1") (pintype "power_in"))
    )
    (net (code "48") (name "Net-(XBEE-ASSOC{slash}AD5{slash}DIO5)") (class "Default")
      (node (ref "R26") (pin "2") (pinfunction "2_2") (pintype "passive"))
      (node (ref "XBEE") (pin "15") (pinfunction "ASSOC/AD5/DIO5_15") (pintype "bidirectional"))
    )
    (net (code "49") (name "Net-(XBEE-ON{slash}~{SLEEP})") (class "Default")
      (node (ref "R28") (pin "2") (pinfunction "2_2") (pintype "passive"))
      (node (ref "XBEE") (pin "13") (pinfunction "ON/~{SLEEP}_13") (pintype "output"))
    )
    (net (code "50") (name "Net-(XBEE-PWM0{slash}RSSI)") (class "Default")
      (node (ref "R27") (pin "2") (pinfunction "2_2") (pintype "passive"))
      (node (ref "XBEE") (pin "6") (pinfunction "PWM0/RSSI_6") (pintype "output"))
    )
    (net (code "51") (name "RST") (class "Default")
      (node (ref "ICSP") (pin "5") (pinfunction "5_5") (pintype "passive"))
      (node (ref "MCU") (pin "13") (pinfunction "~{RESET}_13") (pintype "bidirectional"))
      (node (ref "R23") (pin "2") (pinfunction "2_2") (pintype "passive"))
    )
    (net (code "52") (name "SCK") (class "Default")
      (node (ref "ICSP") (pin "3") (pinfunction "3_3") (pintype "passive"))
      (node (ref "MCU") (pin "9") (pinfunction "PB1(SCK)_9") (pintype "bidirectional"))
    )
    (net (code "53") (name "SCL_BM") (class "Default")
      (node (ref "BM") (pin "6") (pinfunction "SCL_6") (pintype "input"))
      (node (ref "MUX") (pin "20") (pinfunction "SC7_20") (pintype "bidirectional"))
      (node (ref "R22") (pin "1") (pinfunction "1_1") (pintype "passive"))
    )
    (net (code "54") (name "SDA_BM") (class "Default")
      (node (ref "BM") (pin "5") (pinfunction "SDA_5") (pintype "bidirectional"))
      (node (ref "MUX") (pin "19") (pinfunction "SD7_19") (pintype "bidirectional"))
      (node (ref "R21") (pin "1") (pinfunction "1_1") (pintype "passive"))
    )
    (net (code "55") (name "USB_5V0") (class "Default")
      (node (ref "CC") (pin "4") (pinfunction "VIN_4") (pintype "power_in"))
      (node (ref "D1") (pin "A") (pinfunction "A_A") (pintype "passive"))
      (node (ref "D2") (pin "A") (pinfunction "A_A") (pintype "passive"))
      (node (ref "D8") (pin "A") (pinfunction "A_A") (pintype "passive"))
      (node (ref "F1") (pin "2") (pinfunction "2_2") (pintype "bidirectional"))
      (node (ref "Q1") (pin "1") (pinfunction "G_1") (pintype "passive"))
      (node (ref "R29") (pin "2") (pinfunction "2_2") (pintype "passive"))
    )
    (net (code "56") (name "USB_5V0_UF") (class "Default")
      (node (ref "EXT_POWER") (pin "1") (pinfunction "1_1") (pintype "passive"))
      (node (ref "F1") (pin "1") (pinfunction "1_1") (pintype "bidirectional"))
      (node (ref "JP1") (pin "1") (pinfunction "VCC_1") (pintype "power_in"))
    )
    (net (code "57") (name "USB_N") (class "Default")
      (node (ref "MCU") (pin "3") (pinfunction "D-_3") (pintype "bidirectional"))
      (node (ref "R19") (pin "2") (pinfunction "2_2") (pintype "passive"))
    )
    (net (code "58") (name "USB_P") (class "Default")
      (node (ref "MCU") (pin "4") (pinfunction "D+_4") (pintype "bidirectional"))
      (node (ref "R20") (pin "2") (pinfunction "2_2") (pintype "passive"))
    )
    (net (code "59") (name "VCC_3V3") (class "Default")
      (node (ref "BARO") (pin "2") (pinfunction "VS_2") (pintype "power_in"))
      (node (ref "C1") (pin "1") (pinfunction "1_1") (pintype "passive"))
      (node (ref "C15") (pin "2") (pinfunction "2_2") (pintype "passive"))
      (node (ref "C17") (pin "+") (pinfunction "+_+") (pintype "passive"))
      (node (ref "C18") (pin "+") (pinfunction "+_+") (pintype "passive"))
      (node (ref "C19") (pin "+") (pinfunction "+_+") (pintype "passive"))
      (node (ref "C2") (pin "1") (pinfunction "1_1") (pintype "passive"))
      (node (ref "C3") (pin "1") (pinfunction "1_1") (pintype "passive"))
      (node (ref "C4") (pin "1") (pinfunction "1_1") (pintype "passive"))
      (node (ref "C5") (pin "1") (pinfunction "1_1") (pintype "passive"))
      (node (ref "C6") (pin "1") (pinfunction "1_1") (pintype "passive"))
      (node (ref "C7") (pin "+") (pinfunction "+_+") (pintype "passive"))
      (node (ref "C8") (pin "1") (pinfunction "1_1") (pintype "passive"))
      (node (ref "C9") (pin "1") (pinfunction "1_1") (pintype "passive"))
      (node (ref "D3") (pin "A") (pinfunction "A_A") (pintype "passive"))
      (node (ref "D4") (pin "A") (pinfunction "A_A") (pintype "passive"))
      (node (ref "DP0") (pin "2") (pinfunction "VS_2") (pintype "power_in"))
      (node (ref "DPA") (pin "2") (pinfunction "VS_2") (pintype "power_in"))
      (node (ref "DPB") (pin "2") (pinfunction "VS_2") (pintype "power_in"))
      (node (ref "EXT_OAT") (pin "1") (pinfunction "1_1") (pintype "passive"))
      (node (ref "ICSP") (pin "2") (pinfunction "2_2") (pintype "passive"))
      (node (ref "MCU") (pin "14") (pinfunction "VCC_14") (pintype "bidirectional"))
      (node (ref "MCU") (pin "24") (pinfunction "AVCC_24") (pintype "bidirectional"))
      (node (ref "MCU") (pin "34") (pinfunction "VCC_34") (pintype "bidirectional"))
      (node (ref "MCU") (pin "44") (pinfunction "AVCC_44") (pintype "bidirectional"))
      (node (ref "MUX") (pin "24") (pinfunction "VCC_24") (pintype "bidirectional"))
      (node (ref "OAT") (pin "8") (pinfunction "VCC_8") (pintype "power_in"))
      (node (ref "R1") (pin "2") (pinfunction "2_2") (pintype "passive"))
      (node (ref "R10") (pin "2") (pinfunction "2_2") (pintype "passive"))
      (node (ref "R14") (pin "2") (pinfunction "2_2") (pintype "passive"))
      (node (ref "R16") (pin "2") (pinfunction "2_2") (pintype "passive"))
      (node (ref "R17") (pin "2") (pinfunction "2_2") (pintype "passive"))
      (node (ref "R2") (pin "2") (pinfunction "2_2") (pintype "passive"))
      (node (ref "R21") (pin "2") (pinfunction "2_2") (pintype "passive"))
      (node (ref "R22") (pin "2") (pinfunction "2_2") (pintype "passive"))
      (node (ref "R23") (pin "1") (pinfunction "1_1") (pintype "passive"))
      (node (ref "R3") (pin "2") (pinfunction "2_2") (pintype "passive"))
      (node (ref "R4") (pin "2") (pinfunction "2_2") (pintype "passive"))
      (node (ref "R5") (pin "2") (pinfunction "2_2") (pintype "passive"))
      (node (ref "R6") (pin "2") (pinfunction "2_2") (pintype "passive"))
      (node (ref "R7") (pin "2") (pinfunction "2_2") (pintype "passive"))
      (node (ref "R8") (pin "2") (pinfunction "2_2") (pintype "passive"))
      (node (ref "R9") (pin "2") (pinfunction "2_2") (pintype "passive"))
      (node (ref "VREG") (pin "3") (pinfunction "OUT_3") (pintype "power_in"))
      (node (ref "XBEE") (pin "1") (pinfunction "VCC_1") (pintype "power_in"))
    )
    (net (code "60") (name "VCC_5V0") (class "Default")
      (node (ref "C13") (pin "2") (pinfunction "2_2") (pintype "passive"))
      (node (ref "MCU") (pin "2") (pinfunction "UVCC_2") (pintype "bidirectional"))
      (node (ref "MCU") (pin "7") (pinfunction "VBUS_7") (pintype "bidirectional"))
    )
    (net (code "61") (name "unconnected-(BM-PIO-Pad8)") (class "Default")
      (node (ref "BM") (pin "8") (pinfunction "PIO_8") (pintype "bidirectional"))
    )
    (net (code "62") (name "unconnected-(J1-PAD1-PadNC1)") (class "Default")
      (node (ref "J1") (pin "NC1") (pinfunction "PAD1_NC1") (pintype "bidirectional"))
    )
    (net (code "63") (name "unconnected-(J1-PAD2-PadNC2)") (class "Default")
      (node (ref "J1") (pin "NC2") (pinfunction "PAD2_NC2") (pintype "bidirectional"))
    )
    (net (code "64") (name "unconnected-(JP1-ID-Pad4)") (class "Default")
      (node (ref "JP1") (pin "4") (pinfunction "ID_4") (pintype "bidirectional"))
    )
    (net (code "65") (name "unconnected-(MCU-PB4(ADC11)-Pad28)") (class "Default")
      (node (ref "MCU") (pin "28") (pinfunction "PB4(ADC11)_28") (pintype "bidirectional"))
    )
    (net (code "66") (name "unconnected-(MCU-PB5(ADC12)-Pad29)") (class "Default")
      (node (ref "MCU") (pin "29") (pinfunction "PB5(ADC12)_29") (pintype "bidirectional"))
    )
    (net (code "67") (name "unconnected-(MCU-PB6(ADC13)-Pad30)") (class "Default")
      (node (ref "MCU") (pin "30") (pinfunction "PB6(ADC13)_30") (pintype "bidirectional"))
    )
    (net (code "68") (name "unconnected-(MCU-PB7-Pad12)") (class "Default")
      (node (ref "MCU") (pin "12") (pinfunction "PB7_12") (pintype "bidirectional"))
    )
    (net (code "69") (name "unconnected-(MCU-PC6-Pad31)") (class "Default")
      (node (ref "MCU") (pin "31") (pinfunction "PC6_31") (pintype "bidirectional"))
    )
    (net (code "70") (name "unconnected-(MCU-PD6(ADC9)-Pad26)") (class "Default")
      (node (ref "MCU") (pin "26") (pinfunction "PD6(ADC9)_26") (pintype "bidirectional"))
    )
    (net (code "71") (name "unconnected-(MCU-PD7(ADC10)-Pad27)") (class "Default")
      (node (ref "MCU") (pin "27") (pinfunction "PD7(ADC10)_27") (pintype "bidirectional"))
    )
    (net (code "72") (name "unconnected-(MCU-PE6-Pad1)") (class "Default")
      (node (ref "MCU") (pin "1") (pinfunction "PE6_1") (pintype "bidirectional"))
    )
    (net (code "73") (name "unconnected-(MCU-PF1(ADC1)-Pad40)") (class "Default")
      (node (ref "MCU") (pin "40") (pinfunction "PF1(ADC1)_40") (pintype "bidirectional"))
    )
    (net (code "74") (name "unconnected-(MCU-PF4(ADC4)-Pad39)") (class "Default")
      (node (ref "MCU") (pin "39") (pinfunction "PF4(ADC4)_39") (pintype "bidirectional"))
    )
    (net (code "75") (name "unconnected-(MCU-PF5(ADC5)-Pad38)") (class "Default")
      (node (ref "MCU") (pin "38") (pinfunction "PF5(ADC5)_38") (pintype "bidirectional"))
    )
    (net (code "76") (name "unconnected-(MCU-PF6(ADC6)-Pad37)") (class "Default")
      (node (ref "MCU") (pin "37") (pinfunction "PF6(ADC6)_37") (pintype "bidirectional"))
    )
    (net (code "77") (name "unconnected-(MCU-PF7(ADC7)-Pad36)") (class "Default")
      (node (ref "MCU") (pin "36") (pinfunction "PF7(ADC7)_36") (pintype "bidirectional"))
    )
    (net (code "78") (name "unconnected-(MUX-SC5-Pad16)") (class "Default")
      (node (ref "MUX") (pin "16") (pinfunction "SC5_16") (pintype "bidirectional"))
    )
    (net (code "79") (name "unconnected-(MUX-SC6-Pad18)") (class "Default")
      (node (ref "MUX") (pin "18") (pinfunction "SC6_18") (pintype "bidirectional"))
    )
    (net (code "80") (name "unconnected-(MUX-SD5-Pad15)") (class "Default")
      (node (ref "MUX") (pin "15") (pinfunction "SD5_15") (pintype "bidirectional"))
    )
    (net (code "81") (name "unconnected-(MUX-SD6-Pad17)") (class "Default")
      (node (ref "MUX") (pin "17") (pinfunction "SD6_17") (pintype "bidirectional"))
    )
    (net (code "82") (name "unconnected-(OAT-ALERT-Pad3)") (class "Default")
      (node (ref "OAT") (pin "3") (pinfunction "ALERT_3") (pintype "output"))
    )
    (net (code "83") (name "unconnected-(S1-S-Pad3)") (class "Default")
      (node (ref "S1") (pin "3") (pinfunction "S_3") (pintype "passive"))
    )
    (net (code "84") (name "unconnected-(XBEE-AD0{slash}DIO0-Pad20)") (class "Default")
      (node (ref "XBEE") (pin "20") (pinfunction "AD0/DIO0_20") (pintype "bidirectional"))
    )
    (net (code "85") (name "unconnected-(XBEE-AD1{slash}DIO1-Pad19)") (class "Default")
      (node (ref "XBEE") (pin "19") (pinfunction "AD1/DIO1_19") (pintype "bidirectional"))
    )
    (net (code "86") (name "unconnected-(XBEE-AD2{slash}DIO2-Pad18)") (class "Default")
      (node (ref "XBEE") (pin "18") (pinfunction "AD2/DIO2_18") (pintype "bidirectional"))
    )
    (net (code "87") (name "unconnected-(XBEE-CD{slash}DOUT_EN{slash}DO8-Pad4)") (class "Default")
      (node (ref "XBEE") (pin "4") (pinfunction "CD/DOUT_EN/DO8_4") (pintype "output"))
    )
    (net (code "88") (name "unconnected-(XBEE-COORD_SEL{slash}AD3{slash}DIO3-Pad17)") (class "Default")
      (node (ref "XBEE") (pin "17") (pinfunction "COORD_SEL/AD3/DIO3_17") (pintype "bidirectional"))
    )
    (net (code "89") (name "unconnected-(XBEE-RF_TX{slash}AD4{slash}DIO4-Pad11)") (class "Default")
      (node (ref "XBEE") (pin "11") (pinfunction "RF_TX/AD4/DIO4_11") (pintype "bidirectional"))
    )
    (net (code "90") (name "unconnected-(XBEE-VREF-Pad14)") (class "Default")
      (node (ref "XBEE") (pin "14") (pinfunction "VREF_14") (pintype "input"))
    )
    (net (code "91") (name "unconnected-(XBEE-~{CTS}{slash}DIO7-Pad12)") (class "Default")
      (node (ref "XBEE") (pin "12") (pinfunction "~{CTS}/DIO7_12") (pintype "bidirectional"))
    )
    (net (code "92") (name "unconnected-(XBEE-~{RESET}-Pad5)") (class "Default")
      (node (ref "XBEE") (pin "5") (pinfunction "~{RESET}_5") (pintype "input"))
    )
    (net (code "93") (name "unconnected-(XBEE-~{RTS}{slash}AD6{slash}DIO6-Pad16)") (class "Default")
      (node (ref "XBEE") (pin "16") (pinfunction "~{RTS}/AD6/DIO6_16") (pintype "bidirectional"))
    )
  )
)
